# STM32F103RBT6.net
KiCad netlist of a schematic drawn in Altium Designer
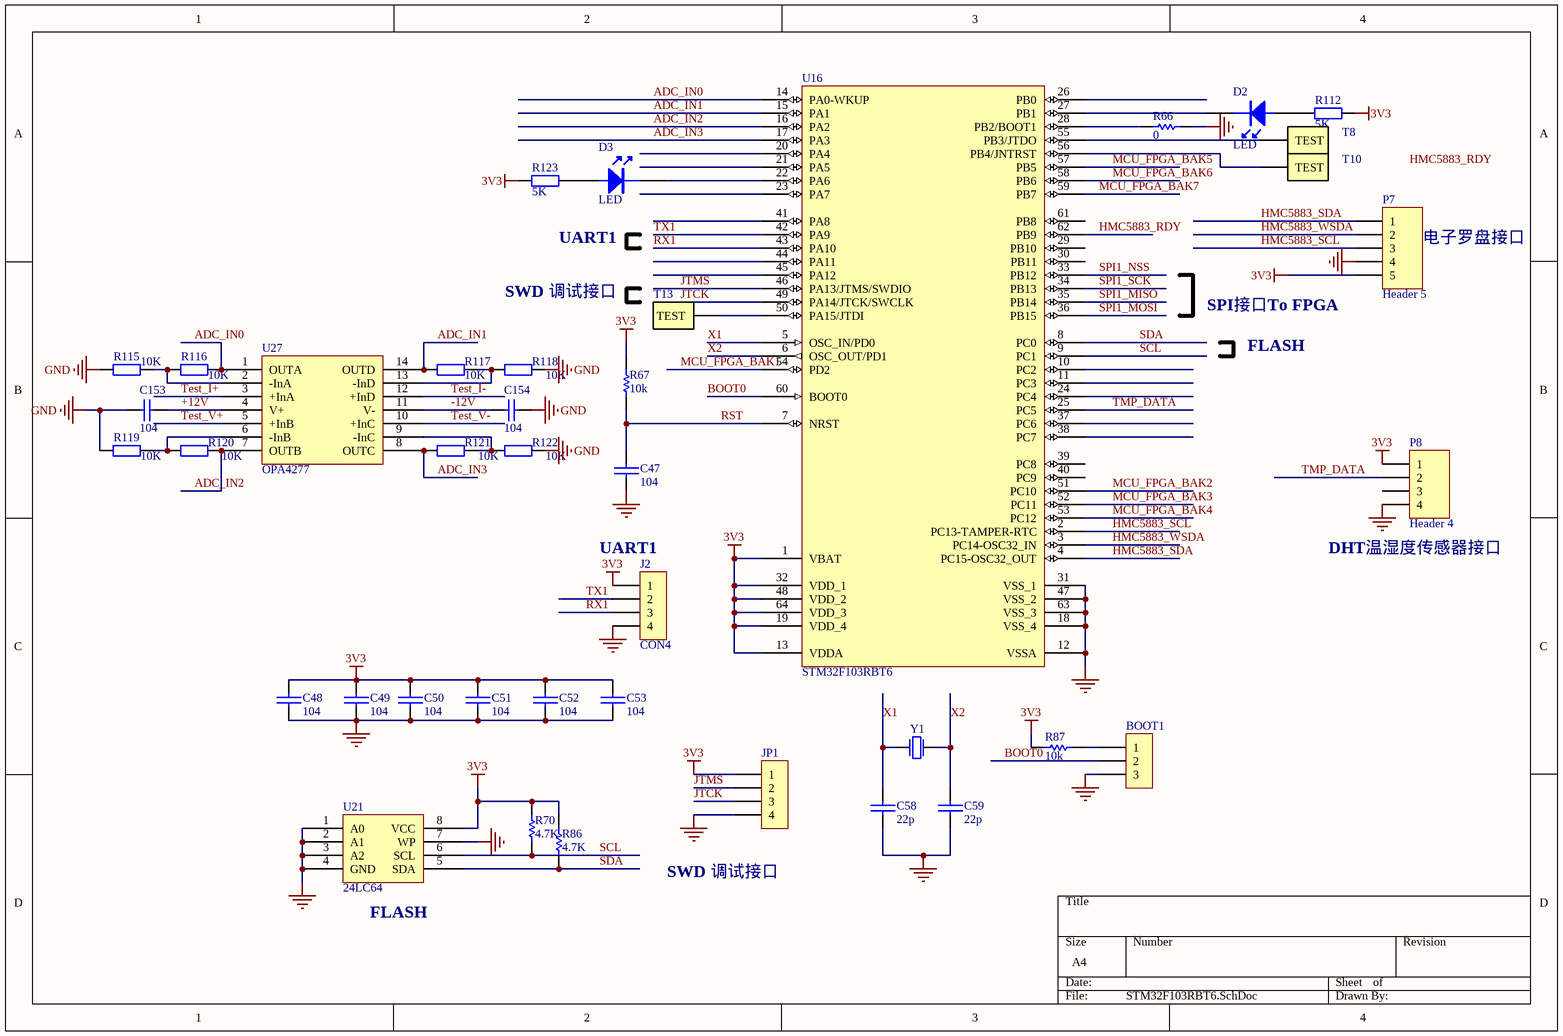
[diagram p0: STM32F103RBT6.SchDoc]

(export (version "E")
  (design (tool "Eeschema 10.0.6"))
  (components
    (comp (ref "BOOT1")
      (value "~")
      (footprint "HDR1X3")
      (description "Connector")
      (libsource (lib "*") (part "CON3"))
    )
    (comp (ref "C47")
      (value "104")
      (footprint "0603")
      (description "Capacitor")
      (libsource (lib "") (part "CAP_1"))
    )
    (comp (ref "C48")
      (value "104")
      (footprint "0603")
      (description "Capacitor")
      (libsource (lib "*") (part "CAP"))
    )
    (comp (ref "C49")
      (value "104")
      (footprint "0603")
      (description "Capacitor")
      (libsource (lib "*") (part "CAP"))
    )
    (comp (ref "C50")
      (value "104")
      (footprint "0603")
      (description "Capacitor")
      (libsource (lib "*") (part "CAP"))
    )
    (comp (ref "C51")
      (value "104")
      (footprint "0603")
      (description "Capacitor")
      (libsource (lib "*") (part "CAP"))
    )
    (comp (ref "C52")
      (value "104")
      (footprint "0603")
      (description "Capacitor")
      (libsource (lib "*") (part "CAP"))
    )
    (comp (ref "C53")
      (value "104")
      (footprint "0603")
      (description "Capacitor")
      (libsource (lib "*") (part "CAP"))
    )
    (comp (ref "C58")
      (value "22p")
      (footprint "0603")
      (description "Capacitor")
      (libsource (lib "*") (part "CAP"))
    )
    (comp (ref "C59")
      (value "22p")
      (footprint "0603")
      (description "Capacitor")
      (libsource (lib "*") (part "CAP"))
    )
    (comp (ref "C153")
      (value "104")
      (footprint "0603")
      (description "Capacitor")
      (fields (field (name "PUBLISHER") "Altium Limited"))
      (libsource (lib "Miscellaneous Devices") (part "Cap"))
    )
    (comp (ref "C154")
      (value "104")
      (footprint "0603")
      (description "Capacitor")
      (fields (field (name "PUBLISHER") "Altium Limited"))
      (libsource (lib "Miscellaneous Devices") (part "Cap"))
    )
    (comp (ref "D2") (value "LED") (footprint "0805_LED") (libsource (lib "*") (part "LED")))
    (comp (ref "D3") (value "LED") (footprint "0805_LED") (libsource (lib "*") (part "LED")))
    (comp (ref "J2")
      (value "CON4")
      (footprint "HDR1X4")
      (description "Connector")
      (libsource (lib "*") (part "CON4"))
    )
    (comp (ref "JP1")
      (value "~")
      (footprint "HDR1X4")
      (description "Connector")
      (libsource (lib "*") (part "CON4"))
    )
    (comp (ref "P7")
      (value "Header 5")
      (footprint "HDR1X5")
      (description "Header, 5-Pin")
      (fields (field (name "PUBLISHER") "Altium Limited"))
      (libsource (lib "Miscellaneous Connectors") (part "Header 5"))
    )
    (comp (ref "P8")
      (value "Header 4")
      (footprint "HDR1X4")
      (description "Header, 4-Pin")
      (fields (field (name "PUBLISHER") "Altium Limited"))
      (libsource (lib "Miscellaneous Connectors") (part "Header 4"))
    )
    (comp (ref "R66")
      (value "0")
      (footprint "0603")
      (description "Resistor")
      (fields (field (name "PUBLISHER") "*"))
      (libsource (lib "*") (part "Res1"))
    )
    (comp (ref "R67")
      (value "10k")
      (footprint "0603")
      (description "Resistor")
      (fields (field (name "PUBLISHER") "*"))
      (libsource (lib "*") (part "res1"))
    )
    (comp (ref "R70")
      (value "4.7K")
      (footprint "0603")
      (description "Resistor")
      (fields (field (name "PUBLISHER") "*"))
      (libsource (lib "*") (part "Res1"))
    )
    (comp (ref "R86")
      (value "4.7K")
      (footprint "0603")
      (description "Resistor")
      (fields (field (name "PUBLISHER") "*"))
      (libsource (lib "*") (part "Res1"))
    )
    (comp (ref "R87")
      (value "10k")
      (footprint "0603")
      (description "Resistor")
      (fields (field (name "PUBLISHER") "*"))
      (libsource (lib "*") (part "res1"))
    )
    (comp (ref "R112")
      (value "5K")
      (footprint "0603")
      (description "Resistor")
      (fields (field (name "Comment") "Res2") (field (name "PUBLISHER") "Altium Limited"))
      (libsource (lib "") (part "Res2_1"))
    )
    (comp (ref "R115")
      (value "10K")
      (footprint "0603")
      (description "Resistor")
      (fields (field (name "Comment") "Res2") (field (name "PUBLISHER") "Altium Limited"))
      (libsource (lib "") (part "Res2_1"))
    )
    (comp (ref "R116")
      (value "10K")
      (footprint "0603")
      (description "Resistor")
      (fields (field (name "Comment") "Res2") (field (name "PUBLISHER") "Altium Limited"))
      (libsource (lib "") (part "Res2_1"))
    )
    (comp (ref "R117")
      (value "10K")
      (footprint "0603")
      (description "Resistor")
      (fields (field (name "Comment") "Res2") (field (name "PUBLISHER") "Altium Limited"))
      (libsource (lib "") (part "Res2_1"))
    )
    (comp (ref "R118")
      (value "10K")
      (footprint "0603")
      (description "Resistor")
      (fields (field (name "Comment") "Res2") (field (name "PUBLISHER") "Altium Limited"))
      (libsource (lib "") (part "Res2_1"))
    )
    (comp (ref "R119")
      (value "10K")
      (footprint "0603")
      (description "Resistor")
      (fields (field (name "Comment") "Res2") (field (name "PUBLISHER") "Altium Limited"))
      (libsource (lib "") (part "Res2_1"))
    )
    (comp (ref "R120")
      (value "10K")
      (footprint "0603")
      (description "Resistor")
      (fields (field (name "Comment") "Res2") (field (name "PUBLISHER") "Altium Limited"))
      (libsource (lib "") (part "Res2_1"))
    )
    (comp (ref "R121")
      (value "10K")
      (footprint "0603")
      (description "Resistor")
      (fields (field (name "Comment") "Res2") (field (name "PUBLISHER") "Altium Limited"))
      (libsource (lib "") (part "Res2_1"))
    )
    (comp (ref "R122")
      (value "10K")
      (footprint "0603")
      (description "Resistor")
      (fields (field (name "Comment") "Res2") (field (name "PUBLISHER") "Altium Limited"))
      (libsource (lib "") (part "Res2_1"))
    )
    (comp (ref "R123")
      (value "5K")
      (footprint "0603")
      (description "Resistor")
      (fields (field (name "Comment") "Res2") (field (name "PUBLISHER") "Altium Limited"))
      (libsource (lib "Miscellaneous Devices") (part "Res2"))
    )
    (comp (ref "T8") (value "~") (footprint "TEST") (libsource (lib "USB30_Project") (part "TEST")))
    (comp (ref "T10") (value "~") (footprint "TEST") (libsource (lib "USB30_Project") (part "TEST")))
    (comp (ref "T13") (value "~") (footprint "TEST") (libsource (lib "") (part "TEST_1")))
    (comp (ref "U16")
      (value "STM32F103RBT6")
      (footprint "LQFP64_M")
      (description "STM32 ARM-based 32-bit MCU with 128 Kbytes Flash, 64-pin LQFP, Industrial Temperature")
      (fields (field (name "PUBLISHER") "*"))
      (libsource (lib "*") (part "STM32F103RBT6"))
    )
    (comp (ref "U21") (value "24LC64") (footprint "SO8") (libsource (lib "*") (part "24C02")))
    (comp (ref "U27") (value "OPA4277") (footprint "SOP14") (libsource (lib "Schlib1") (part "OPA4277")))
    (comp (ref "Y1")
      (value "~")
      (footprint "XTAL_8M")
      (description "Crystal Oscillator")
      (libsource (lib "*") (part "XTAL"))
    )
  )
  (nets
    (net (code "1") (name "/+12V") (class "Default")
      (node (ref "C153") (pin "2") (pinfunction "2_2") (pintype "passive"))
      (node (ref "U27") (pin "4") (pinfunction "V+_4") (pintype "passive"))
    )
    (net (code "2") (name "/-12V") (class "Default")
      (node (ref "C154") (pin "1") (pinfunction "1_1") (pintype "passive"))
      (node (ref "U27") (pin "11") (pinfunction "V-_11") (pintype "passive"))
    )
    (net (code "3") (name "/ADC_IN0") (class "Default")
      (node (ref "R116") (pin "2") (pinfunction "2_2") (pintype "passive"))
      (node (ref "U16") (pin "14") (pinfunction "PA0-WKUP_14") (pintype "bidirectional"))
      (node (ref "U27") (pin "1") (pinfunction "OUTA_1") (pintype "passive"))
    )
    (net (code "4") (name "/ADC_IN1") (class "Default")
      (node (ref "R117") (pin "1") (pinfunction "1_1") (pintype "passive"))
      (node (ref "U16") (pin "15") (pinfunction "PA1_15") (pintype "bidirectional"))
      (node (ref "U27") (pin "14") (pinfunction "OUTD_14") (pintype "passive"))
    )
    (net (code "5") (name "/ADC_IN2") (class "Default")
      (node (ref "R120") (pin "2") (pinfunction "2_2") (pintype "passive"))
      (node (ref "U16") (pin "16") (pinfunction "PA2_16") (pintype "bidirectional"))
      (node (ref "U27") (pin "7") (pinfunction "OUTB_7") (pintype "passive"))
    )
    (net (code "6") (name "/ADC_IN3") (class "Default")
      (node (ref "R121") (pin "1") (pinfunction "1_1") (pintype "passive"))
      (node (ref "U16") (pin "17") (pinfunction "PA3_17") (pintype "bidirectional"))
      (node (ref "U27") (pin "8") (pinfunction "OUTC_8") (pintype "passive"))
    )
    (net (code "7") (name "/BOOT0") (class "Default")
      (node (ref "BOOT1") (pin "2") (pinfunction "2_2") (pintype "passive"))
      (node (ref "U16") (pin "60") (pinfunction "BOOT0_60") (pintype "input"))
    )
    (net (code "8") (name "/HMC5883_RDY") (class "Default")
      (node (ref "U16") (pin "62") (pinfunction "PB9_62") (pintype "bidirectional"))
    )
    (net (code "9") (name "/HMC5883_SCL") (class "Default")
      (node (ref "P7") (pin "3") (pinfunction "3_3") (pintype "passive"))
      (node (ref "U16") (pin "2") (pinfunction "PC13-TAMPER-RTC_2") (pintype "bidirectional"))
    )
    (net (code "10") (name "/HMC5883_SDA") (class "Default")
      (node (ref "P7") (pin "1") (pinfunction "1_1") (pintype "passive"))
      (node (ref "U16") (pin "4") (pinfunction "PC15-OSC32_OUT_4") (pintype "bidirectional"))
    )
    (net (code "11") (name "/HMC5883_WSDA") (class "Default")
      (node (ref "P7") (pin "2") (pinfunction "2_2") (pintype "passive"))
      (node (ref "U16") (pin "3") (pinfunction "PC14-OSC32_IN_3") (pintype "bidirectional"))
    )
    (net (code "12") (name "/JTCK") (class "Default")
      (node (ref "JP1") (pin "3") (pinfunction "3_3") (pintype "passive"))
      (node (ref "U16") (pin "49") (pinfunction "PA14/JTCK/SWCLK_49") (pintype "bidirectional"))
    )
    (net (code "13") (name "/JTMS") (class "Default")
      (node (ref "JP1") (pin "2") (pinfunction "2_2") (pintype "passive"))
      (node (ref "U16") (pin "46") (pinfunction "PA13/JTMS/SWDIO_46") (pintype "bidirectional"))
    )
    (net (code "14") (name "/MCU_FPGA_BAK1") (class "Default")
      (node (ref "U16") (pin "54") (pinfunction "PD2_54") (pintype "bidirectional"))
    )
    (net (code "15") (name "/MCU_FPGA_BAK2") (class "Default")
      (node (ref "U16") (pin "51") (pinfunction "PC10_51") (pintype "bidirectional"))
    )
    (net (code "16") (name "/MCU_FPGA_BAK3") (class "Default")
      (node (ref "U16") (pin "52") (pinfunction "PC11_52") (pintype "bidirectional"))
    )
    (net (code "17") (name "/MCU_FPGA_BAK4") (class "Default")
      (node (ref "U16") (pin "53") (pinfunction "PC12_53") (pintype "bidirectional"))
    )
    (net (code "18") (name "/MCU_FPGA_BAK5") (class "Default")
      (node (ref "U16") (pin "57") (pinfunction "PB5_57") (pintype "bidirectional"))
    )
    (net (code "19") (name "/MCU_FPGA_BAK6") (class "Default")
      (node (ref "U16") (pin "58") (pinfunction "PB6_58") (pintype "bidirectional"))
    )
    (net (code "20") (name "/MCU_FPGA_BAK7") (class "Default")
      (node (ref "U16") (pin "59") (pinfunction "PB7_59") (pintype "bidirectional"))
    )
    (net (code "21") (name "/RST") (class "Default")
      (node (ref "C47") (pin "1") (pinfunction "1_1") (pintype "passive"))
      (node (ref "R67") (pin "1") (pinfunction "1_1") (pintype "passive"))
      (node (ref "U16") (pin "7") (pinfunction "NRST_7") (pintype "bidirectional"))
    )
    (net (code "22") (name "/RX1") (class "Default")
      (node (ref "J2") (pin "3") (pinfunction "3_3") (pintype "passive"))
      (node (ref "U16") (pin "43") (pinfunction "PA10_43") (pintype "bidirectional"))
    )
    (net (code "23") (name "/SCL") (class "Default")
      (node (ref "R70") (pin "1") (pinfunction "1_1") (pintype "passive"))
      (node (ref "U16") (pin "9") (pinfunction "PC1_9") (pintype "bidirectional"))
      (node (ref "U21") (pin "6") (pinfunction "SCL_6") (pintype "passive"))
    )
    (net (code "24") (name "/SDA") (class "Default")
      (node (ref "R86") (pin "1") (pinfunction "1_1") (pintype "passive"))
      (node (ref "U16") (pin "8") (pinfunction "PC0_8") (pintype "bidirectional"))
      (node (ref "U21") (pin "5") (pinfunction "SDA_5") (pintype "passive"))
    )
    (net (code "25") (name "/SPI1_MISO") (class "Default")
      (node (ref "U16") (pin "35") (pinfunction "PB14_35") (pintype "bidirectional"))
    )
    (net (code "26") (name "/SPI1_MOSI") (class "Default")
      (node (ref "U16") (pin "36") (pinfunction "PB15_36") (pintype "bidirectional"))
    )
    (net (code "27") (name "/SPI1_NSS") (class "Default")
      (node (ref "U16") (pin "33") (pinfunction "PB12_33") (pintype "bidirectional"))
    )
    (net (code "28") (name "/SPI1_SCK") (class "Default")
      (node (ref "U16") (pin "34") (pinfunction "PB13_34") (pintype "bidirectional"))
    )
    (net (code "29") (name "/TMP_DATA") (class "Default")
      (node (ref "P8") (pin "2") (pinfunction "2_2") (pintype "passive"))
      (node (ref "U16") (pin "25") (pinfunction "PC5_25") (pintype "bidirectional"))
    )
    (net (code "30") (name "/TX1") (class "Default")
      (node (ref "J2") (pin "2") (pinfunction "2_2") (pintype "passive"))
      (node (ref "U16") (pin "42") (pinfunction "PA9_42") (pintype "bidirectional"))
    )
    (net (code "31") (name "/Test_I+") (class "Default")
      (node (ref "U27") (pin "3") (pinfunction "+InA_3") (pintype "passive"))
    )
    (net (code "32") (name "/Test_I-") (class "Default")
      (node (ref "U27") (pin "12") (pinfunction "+InD_12") (pintype "passive"))
    )
    (net (code "33") (name "/Test_V+") (class "Default")
      (node (ref "U27") (pin "5") (pinfunction "+InB_5") (pintype "passive"))
    )
    (net (code "34") (name "/Test_V-") (class "Default")
      (node (ref "U27") (pin "10") (pinfunction "+InC_10") (pintype "passive"))
    )
    (net (code "35") (name "/X1") (class "Default")
      (node (ref "C58") (pin "1") (pinfunction "1_1") (pintype "passive"))
      (node (ref "U16") (pin "5") (pinfunction "OSC_IN/PD0_5") (pintype "input"))
      (node (ref "Y1") (pin "2") (pinfunction "P2_2") (pintype "passive"))
    )
    (net (code "36") (name "/X2") (class "Default")
      (node (ref "C59") (pin "1") (pinfunction "1_1") (pintype "passive"))
      (node (ref "U16") (pin "6") (pinfunction "OSC_OUT/PD1_6") (pintype "output"))
      (node (ref "Y1") (pin "1") (pinfunction "P1_1") (pintype "passive"))
    )
    (net (code "37") (name "3V3") (class "Default")
      (node (ref "C48") (pin "1") (pinfunction "1_1") (pintype "passive"))
      (node (ref "C49") (pin "1") (pinfunction "1_1") (pintype "passive"))
      (node (ref "C50") (pin "1") (pinfunction "1_1") (pintype "passive"))
      (node (ref "C51") (pin "1") (pinfunction "1_1") (pintype "passive"))
      (node (ref "C52") (pin "1") (pinfunction "1_1") (pintype "passive"))
      (node (ref "C53") (pin "1") (pinfunction "1_1") (pintype "passive"))
      (node (ref "J2") (pin "1") (pinfunction "1_1") (pintype "passive"))
      (node (ref "JP1") (pin "1") (pinfunction "1_1") (pintype "passive"))
      (node (ref "P7") (pin "5") (pinfunction "5_5") (pintype "passive"))
      (node (ref "P8") (pin "1") (pinfunction "1_1") (pintype "passive"))
      (node (ref "R112") (pin "2") (pinfunction "2_2") (pintype "passive"))
      (node (ref "R123") (pin "2") (pinfunction "2_2") (pintype "passive"))
      (node (ref "R67") (pin "2") (pinfunction "2_2") (pintype "passive"))
      (node (ref "R70") (pin "2") (pinfunction "2_2") (pintype "passive"))
      (node (ref "R86") (pin "2") (pinfunction "2_2") (pintype "passive"))
      (node (ref "R87") (pin "1") (pinfunction "1_1") (pintype "passive"))
      (node (ref "U16") (pin "1") (pinfunction "VBAT_1") (pintype "power_in"))
      (node (ref "U16") (pin "13") (pinfunction "VDDA_13") (pintype "power_in"))
      (node (ref "U16") (pin "19") (pinfunction "VDD_4_19") (pintype "power_in"))
      (node (ref "U16") (pin "32") (pinfunction "VDD_1_32") (pintype "power_in"))
      (node (ref "U16") (pin "48") (pinfunction "VDD_2_48") (pintype "power_in"))
      (node (ref "U16") (pin "64") (pinfunction "VDD_3_64") (pintype "power_in"))
      (node (ref "U21") (pin "8") (pinfunction "VCC_8") (pintype "passive"))
    )
    (net (code "38") (name "GND") (class "Default")
      (node (ref "BOOT1") (pin "3") (pinfunction "3_3") (pintype "passive"))
      (node (ref "C153") (pin "1") (pinfunction "1_1") (pintype "passive"))
      (node (ref "C154") (pin "2") (pinfunction "2_2") (pintype "passive"))
      (node (ref "C47") (pin "2") (pinfunction "2_2") (pintype "passive"))
      (node (ref "C48") (pin "2") (pinfunction "2_2") (pintype "passive"))
      (node (ref "C49") (pin "2") (pinfunction "2_2") (pintype "passive"))
      (node (ref "C50") (pin "2") (pinfunction "2_2") (pintype "passive"))
      (node (ref "C51") (pin "2") (pinfunction "2_2") (pintype "passive"))
      (node (ref "C52") (pin "2") (pinfunction "2_2") (pintype "passive"))
      (node (ref "C53") (pin "2") (pinfunction "2_2") (pintype "passive"))
      (node (ref "C58") (pin "2") (pinfunction "2_2") (pintype "passive"))
      (node (ref "C59") (pin "2") (pinfunction "2_2") (pintype "passive"))
      (node (ref "J2") (pin "4") (pinfunction "4_4") (pintype "passive"))
      (node (ref "JP1") (pin "4") (pinfunction "4_4") (pintype "passive"))
      (node (ref "P7") (pin "4") (pinfunction "4_4") (pintype "passive"))
      (node (ref "P8") (pin "4") (pinfunction "4_4") (pintype "passive"))
      (node (ref "R115") (pin "1") (pinfunction "1_1") (pintype "passive"))
      (node (ref "R118") (pin "2") (pinfunction "2_2") (pintype "passive"))
      (node (ref "R119") (pin "1") (pinfunction "1_1") (pintype "passive"))
      (node (ref "R122") (pin "2") (pinfunction "2_2") (pintype "passive"))
      (node (ref "R66") (pin "2") (pinfunction "2_2") (pintype "passive"))
      (node (ref "U16") (pin "12") (pinfunction "VSSA_12") (pintype "power_in"))
      (node (ref "U16") (pin "18") (pinfunction "VSS_4_18") (pintype "power_in"))
      (node (ref "U16") (pin "31") (pinfunction "VSS_1_31") (pintype "power_in"))
      (node (ref "U16") (pin "47") (pinfunction "VSS_2_47") (pintype "power_in"))
      (node (ref "U16") (pin "63") (pinfunction "VSS_3_63") (pintype "power_in"))
      (node (ref "U21") (pin "1") (pinfunction "A0_1") (pintype "passive"))
      (node (ref "U21") (pin "2") (pinfunction "A1_2") (pintype "passive"))
      (node (ref "U21") (pin "3") (pinfunction "A2_3") (pintype "passive"))
      (node (ref "U21") (pin "4") (pinfunction "GND_4") (pintype "passive"))
      (node (ref "U21") (pin "7") (pinfunction "WP_7") (pintype "passive"))
    )
    (net (code "39") (name "Net-(BOOT1-Pad1)") (class "Default")
      (node (ref "BOOT1") (pin "1") (pinfunction "1_1") (pintype "passive"))
      (node (ref "R87") (pin "2") (pinfunction "2_2") (pintype "passive"))
    )
    (net (code "40") (name "Net-(D2-A)") (class "Default")
      (node (ref "D2") (pin "1") (pinfunction "A_1") (pintype "passive"))
      (node (ref "R112") (pin "1") (pinfunction "1_1") (pintype "passive"))
    )
    (net (code "41") (name "Net-(D2-K)") (class "Default")
      (node (ref "D2") (pin "2") (pinfunction "K_2") (pintype "passive"))
      (node (ref "U16") (pin "27") (pinfunction "PB1_27") (pintype "bidirectional"))
    )
    (net (code "42") (name "Net-(D3-A)") (class "Default")
      (node (ref "D3") (pin "1") (pinfunction "A_1") (pintype "passive"))
      (node (ref "R123") (pin "1") (pinfunction "1_1") (pintype "passive"))
    )
    (net (code "43") (name "Net-(D3-K)") (class "Default")
      (node (ref "D3") (pin "2") (pinfunction "K_2") (pintype "passive"))
      (node (ref "U16") (pin "22") (pinfunction "PA6_22") (pintype "bidirectional"))
    )
    (net (code "44") (name "Net-(T8-TEST)") (class "Default")
      (node (ref "T8") (pin "1") (pinfunction "TEST_1") (pintype "passive"))
      (node (ref "U16") (pin "55") (pinfunction "PB3/JTDO_55") (pintype "bidirectional"))
    )
    (net (code "45") (name "Net-(T10-TEST)") (class "Default")
      (node (ref "T10") (pin "1") (pinfunction "TEST_1") (pintype "passive"))
      (node (ref "U16") (pin "56") (pinfunction "PB4/JNTRST_56") (pintype "bidirectional"))
    )
    (net (code "46") (name "Net-(T13-TEST)") (class "Default")
      (node (ref "T13") (pin "1") (pinfunction "TEST_1") (pintype "passive"))
      (node (ref "U16") (pin "50") (pinfunction "PA15/JTDI_50") (pintype "bidirectional"))
    )
    (net (code "47") (name "Net-(U16-PB2{slash}BOOT1)") (class "Default")
      (node (ref "R66") (pin "1") (pinfunction "1_1") (pintype "passive"))
      (node (ref "U16") (pin "28") (pinfunction "PB2/BOOT1_28") (pintype "bidirectional"))
    )
    (net (code "48") (name "Net-(U27--InA)") (class "Default")
      (node (ref "R115") (pin "2") (pinfunction "2_2") (pintype "passive"))
      (node (ref "R116") (pin "1") (pinfunction "1_1") (pintype "passive"))
      (node (ref "U27") (pin "2") (pinfunction "-InA_2") (pintype "passive"))
    )
    (net (code "49") (name "Net-(U27--InB)") (class "Default")
      (node (ref "R119") (pin "2") (pinfunction "2_2") (pintype "passive"))
      (node (ref "R120") (pin "1") (pinfunction "1_1") (pintype "passive"))
      (node (ref "U27") (pin "6") (pinfunction "-InB_6") (pintype "passive"))
    )
    (net (code "50") (name "Net-(U27--InC)") (class "Default")
      (node (ref "R121") (pin "2") (pinfunction "2_2") (pintype "passive"))
      (node (ref "R122") (pin "1") (pinfunction "1_1") (pintype "passive"))
      (node (ref "U27") (pin "9") (pinfunction "-InC_9") (pintype "passive"))
    )
    (net (code "51") (name "Net-(U27--InD)") (class "Default")
      (node (ref "R117") (pin "2") (pinfunction "2_2") (pintype "passive"))
      (node (ref "R118") (pin "1") (pinfunction "1_1") (pintype "passive"))
      (node (ref "U27") (pin "13") (pinfunction "-InD_13") (pintype "passive"))
    )
    (net (code "52") (name "unconnected-(P8-Pad3)") (class "Default")
      (node (ref "P8") (pin "3") (pinfunction "3_3") (pintype "passive"))
    )
    (net (code "53") (name "unconnected-(U16-PA4-Pad20)") (class "Default")
      (node (ref "U16") (pin "20") (pinfunction "PA4_20") (pintype "bidirectional"))
    )
    (net (code "54") (name "unconnected-(U16-PA5-Pad21)") (class "Default")
      (node (ref "U16") (pin "21") (pinfunction "PA5_21") (pintype "bidirectional"))
    )
    (net (code "55") (name "unconnected-(U16-PA7-Pad23)") (class "Default")
      (node (ref "U16") (pin "23") (pinfunction "PA7_23") (pintype "bidirectional"))
    )
    (net (code "56") (name "unconnected-(U16-PA8-Pad41)") (class "Default")
      (node (ref "U16") (pin "41") (pinfunction "PA8_41") (pintype "bidirectional"))
    )
    (net (code "57") (name "unconnected-(U16-PA11-Pad44)") (class "Default")
      (node (ref "U16") (pin "44") (pinfunction "PA11_44") (pintype "bidirectional"))
    )
    (net (code "58") (name "unconnected-(U16-PA12-Pad45)") (class "Default")
      (node (ref "U16") (pin "45") (pinfunction "PA12_45") (pintype "bidirectional"))
    )
    (net (code "59") (name "unconnected-(U16-PB0-Pad26)") (class "Default")
      (node (ref "U16") (pin "26") (pinfunction "PB0_26") (pintype "bidirectional"))
    )
    (net (code "60") (name "unconnected-(U16-PB8-Pad61)") (class "Default")
      (node (ref "U16") (pin "61") (pinfunction "PB8_61") (pintype "bidirectional"))
    )
    (net (code "61") (name "unconnected-(U16-PB10-Pad29)") (class "Default")
      (node (ref "U16") (pin "29") (pinfunction "PB10_29") (pintype "bidirectional"))
    )
    (net (code "62") (name "unconnected-(U16-PB11-Pad30)") (class "Default")
      (node (ref "U16") (pin "30") (pinfunction "PB11_30") (pintype "bidirectional"))
    )
    (net (code "63") (name "unconnected-(U16-PC2-Pad10)") (class "Default")
      (node (ref "U16") (pin "10") (pinfunction "PC2_10") (pintype "bidirectional"))
    )
    (net (code "64") (name "unconnected-(U16-PC3-Pad11)") (class "Default")
      (node (ref "U16") (pin "11") (pinfunction "PC3_11") (pintype "bidirectional"))
    )
    (net (code "65") (name "unconnected-(U16-PC4-Pad24)") (class "Default")
      (node (ref "U16") (pin "24") (pinfunction "PC4_24") (pintype "bidirectional"))
    )
    (net (code "66") (name "unconnected-(U16-PC6-Pad37)") (class "Default")
      (node (ref "U16") (pin "37") (pinfunction "PC6_37") (pintype "bidirectional"))
    )
    (net (code "67") (name "unconnected-(U16-PC7-Pad38)") (class "Default")
      (node (ref "U16") (pin "38") (pinfunction "PC7_38") (pintype "bidirectional"))
    )
    (net (code "68") (name "unconnected-(U16-PC8-Pad39)") (class "Default")
      (node (ref "U16") (pin "39") (pinfunction "PC8_39") (pintype "bidirectional"))
    )
    (net (code "69") (name "unconnected-(U16-PC9-Pad40)") (class "Default")
      (node (ref "U16") (pin "40") (pinfunction "PC9_40") (pintype "bidirectional"))
    )
  )
)
